# axiom_beta_plugin_module_1xHDMI_v0_2_543.net
KiCad netlist of a schematic drawn in EAGLE
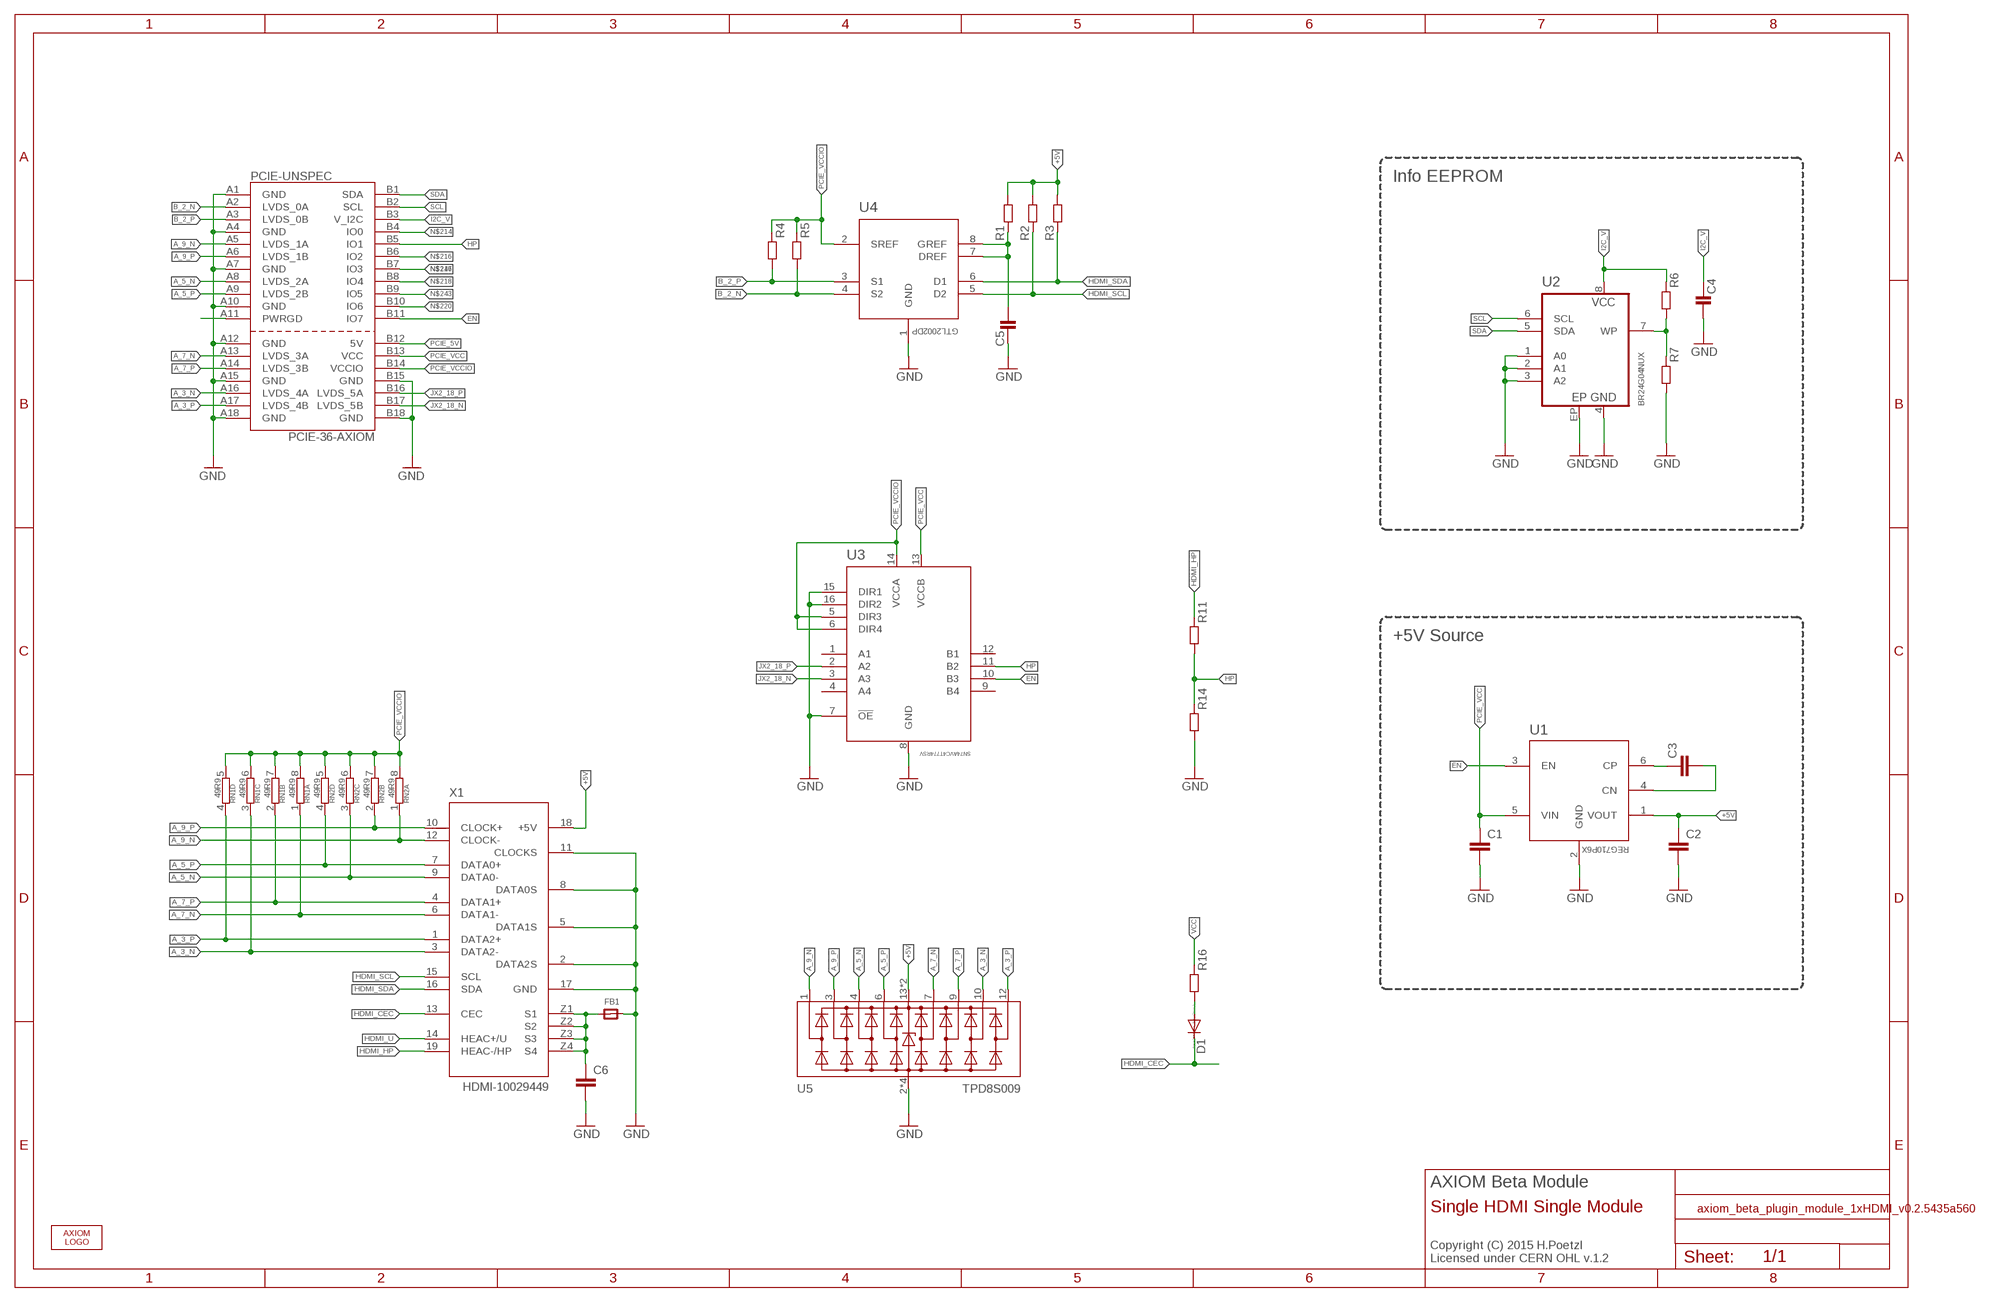
[diagram p0: schematic, sheet 1]

(export (version "E")
  (design (tool "Eeschema 10.0.6"))
  (components
    (comp (ref "C1")
      (value "C-EUC0603K")
      (footprint "eagle-import:C0603K")
      (libsource (lib "eagle-import") (part "C-EUC0603K"))
    )
    (comp (ref "C2")
      (value "C-EUC0603K")
      (footprint "eagle-import:C0603K")
      (libsource (lib "eagle-import") (part "C-EUC0603K"))
    )
    (comp (ref "C3")
      (value "C-EUC0603K")
      (footprint "eagle-import:C0603K")
      (libsource (lib "eagle-import") (part "C-EUC0603K"))
    )
    (comp (ref "C4")
      (value "C0402-B")
      (footprint "eagle-import:0402-B")
      (libsource (lib "eagle-import") (part "C0402-B"))
    )
    (comp (ref "C5")
      (value "C0402-B")
      (footprint "eagle-import:0402-B")
      (libsource (lib "eagle-import") (part "C0402-B"))
    )
    (comp (ref "C6")
      (value "C-EUC0603K")
      (footprint "eagle-import:C0603K")
      (libsource (lib "eagle-import") (part "C-EUC0603K"))
    )
    (comp (ref "D1")
      (value "DIODE-SOD523")
      (footprint "eagle-import:SOD523")
      (libsource (lib "eagle-import") (part "DIODE-SOD523"))
    )
    (comp (ref "FB1")
      (value "FERRITE_0603MP")
      (footprint "eagle-import:_0603MP")
      (libsource (lib "eagle-import") (part "FERRITE_0603MP"))
    )
    (comp (ref "PCIE-UNSPEC")
      (value "PCIE-36-AXIOM")
      (footprint "eagle-import:PCIE-36-AXIOM")
      (libsource (lib "eagle-import") (part "PCIE-36-AXIOM"))
    )
    (comp (ref "R1")
      (value "R0402-B")
      (footprint "eagle-import:0402-B")
      (libsource (lib "eagle-import") (part "R0402-B"))
    )
    (comp (ref "R2")
      (value "R0402-B")
      (footprint "eagle-import:0402-B")
      (libsource (lib "eagle-import") (part "R0402-B"))
    )
    (comp (ref "R3")
      (value "R0402-B")
      (footprint "eagle-import:0402-B")
      (libsource (lib "eagle-import") (part "R0402-B"))
    )
    (comp (ref "R4")
      (value "R0402-B")
      (footprint "eagle-import:0402-B")
      (libsource (lib "eagle-import") (part "R0402-B"))
    )
    (comp (ref "R5")
      (value "R0402-B")
      (footprint "eagle-import:0402-B")
      (libsource (lib "eagle-import") (part "R0402-B"))
    )
    (comp (ref "R6")
      (value "R0402-B")
      (footprint "eagle-import:0402-B")
      (libsource (lib "eagle-import") (part "R0402-B"))
    )
    (comp (ref "R7")
      (value "R0603-B")
      (footprint "eagle-import:0603-B")
      (libsource (lib "eagle-import") (part "R0603-B"))
    )
    (comp (ref "R11")
      (value "R0402-B")
      (footprint "eagle-import:0402-B")
      (libsource (lib "eagle-import") (part "R0402-B"))
    )
    (comp (ref "R14")
      (value "R0402-B")
      (footprint "eagle-import:0402-B")
      (libsource (lib "eagle-import") (part "R0402-B"))
    )
    (comp (ref "R16")
      (value "R0402-B")
      (footprint "eagle-import:0402-B")
      (libsource (lib "eagle-import") (part "R0402-B"))
    )
    (comp (ref "RN1")
      (value "49R9")
      (footprint "eagle-import:CAY16")
      (libsource (lib "eagle-import") (part "4R-NCAY16"))
    )
    (comp (ref "RN2")
      (value "49R9")
      (footprint "eagle-import:CAY16")
      (libsource (lib "eagle-import") (part "4R-NCAY16"))
    )
    (comp (ref "U$1")
      (value "AXIOM_LOGO262X40")
      (footprint "eagle-import:AXIOM_LOGO_262X40")
      (libsource (lib "eagle-import") (part "AXIOM_LOGO262X40"))
    )
    (comp (ref "U1")
      (value "REG710P6X")
      (footprint "eagle-import:SOT65P210X110-6N")
      (libsource (lib "eagle-import") (part "REG710P6X"))
    )
    (comp (ref "U2")
      (value "BR24G04NUX")
      (footprint "eagle-import:DFN200X300X100-9N")
      (libsource (lib "eagle-import") (part "BR24G04NUX"))
    )
    (comp (ref "U3")
      (value "SN74AVC4T774RSV")
      (footprint "eagle-import:QFN40P185X265X55-16N")
      (libsource (lib "eagle-import") (part "SN74AVC4T774RSV"))
    )
    (comp (ref "U4")
      (value "GTL2002DP")
      (footprint "eagle-import:TSSOP-8")
      (libsource (lib "eagle-import") (part "GTL2002DP"))
    )
    (comp (ref "U5")
      (value "TPD8S009")
      (footprint "eagle-import:R-PDSO-N15")
      (libsource (lib "eagle-import") (part "TPD8S009"))
    )
    (comp (ref "X1")
      (value "HDMI-10029449")
      (footprint "eagle-import:10029449-X01XLF")
      (libsource (lib "eagle-import") (part "HDMI-10029449"))
    )
  )
  (nets
    (net (code "1") (name "+5V") (class "Default")
      (node (ref "C2") (pin "1") (pinfunction "1_1") (pintype "passive"))
      (node (ref "R1") (pin "2") (pinfunction "2_2") (pintype "passive"))
      (node (ref "R2") (pin "2") (pinfunction "2_2") (pintype "passive"))
      (node (ref "R3") (pin "2") (pinfunction "2_2") (pintype "passive"))
      (node (ref "U1") (pin "1") (pinfunction "VOUT_1") (pintype "output"))
      (node (ref "U5") (pin "13") (pinfunction "VCC_13") (pintype "power_in"))
      (node (ref "U5") (pin "15") (pinfunction "VCC_15") (pintype "power_in"))
      (node (ref "X1") (pin "18") (pinfunction "+5V_18") (pintype "power_in"))
    )
    (net (code "2") (name "A_3_N") (class "Default")
      (node (ref "PCIE-UNSPEC") (pin "A16") (pinfunction "LVDS_4A_A16") (pintype "passive"))
      (node (ref "RN1") (pin "3") (pinfunction "1_3") (pintype "passive"))
      (node (ref "U5") (pin "10") (pinfunction "ESD7_10") (pintype "passive"))
      (node (ref "X1") (pin "3") (pinfunction "DATA2-_3") (pintype "bidirectional"))
    )
    (net (code "3") (name "A_3_P") (class "Default")
      (node (ref "PCIE-UNSPEC") (pin "A17") (pinfunction "LVDS_4B_A17") (pintype "passive"))
      (node (ref "RN1") (pin "4") (pinfunction "1_4") (pintype "passive"))
      (node (ref "U5") (pin "12") (pinfunction "ESD8_12") (pintype "passive"))
      (node (ref "X1") (pin "1") (pinfunction "DATA2+_1") (pintype "bidirectional"))
    )
    (net (code "4") (name "A_5_N") (class "Default")
      (node (ref "PCIE-UNSPEC") (pin "A8") (pinfunction "LVDS_2A_A8") (pintype "passive"))
      (node (ref "RN2") (pin "3") (pinfunction "1_3") (pintype "passive"))
      (node (ref "U5") (pin "4") (pinfunction "ESD3_4") (pintype "passive"))
      (node (ref "X1") (pin "9") (pinfunction "DATA0-_9") (pintype "bidirectional"))
    )
    (net (code "5") (name "A_5_P") (class "Default")
      (node (ref "PCIE-UNSPEC") (pin "A9") (pinfunction "LVDS_2B_A9") (pintype "passive"))
      (node (ref "RN2") (pin "4") (pinfunction "1_4") (pintype "passive"))
      (node (ref "U5") (pin "6") (pinfunction "ESD4_6") (pintype "passive"))
      (node (ref "X1") (pin "7") (pinfunction "DATA0+_7") (pintype "bidirectional"))
    )
    (net (code "6") (name "A_7_N") (class "Default")
      (node (ref "PCIE-UNSPEC") (pin "A13") (pinfunction "LVDS_3A_A13") (pintype "passive"))
      (node (ref "RN1") (pin "1") (pinfunction "1_1") (pintype "passive"))
      (node (ref "U5") (pin "7") (pinfunction "ESD5_7") (pintype "passive"))
      (node (ref "X1") (pin "6") (pinfunction "DATA1-_6") (pintype "bidirectional"))
    )
    (net (code "7") (name "A_7_P") (class "Default")
      (node (ref "PCIE-UNSPEC") (pin "A14") (pinfunction "LVDS_3B_A14") (pintype "passive"))
      (node (ref "RN1") (pin "2") (pinfunction "1_2") (pintype "passive"))
      (node (ref "U5") (pin "9") (pinfunction "ESD6_9") (pintype "passive"))
      (node (ref "X1") (pin "4") (pinfunction "DATA1+_4") (pintype "bidirectional"))
    )
    (net (code "8") (name "A_9_N") (class "Default")
      (node (ref "PCIE-UNSPEC") (pin "A5") (pinfunction "LVDS_1A_A5") (pintype "passive"))
      (node (ref "RN2") (pin "1") (pinfunction "1_1") (pintype "passive"))
      (node (ref "U5") (pin "1") (pinfunction "ESD1_1") (pintype "passive"))
      (node (ref "X1") (pin "12") (pinfunction "CLOCK-_12") (pintype "bidirectional"))
    )
    (net (code "9") (name "A_9_P") (class "Default")
      (node (ref "PCIE-UNSPEC") (pin "A6") (pinfunction "LVDS_1B_A6") (pintype "passive"))
      (node (ref "RN2") (pin "2") (pinfunction "1_2") (pintype "passive"))
      (node (ref "U5") (pin "3") (pinfunction "ESD2_3") (pintype "passive"))
      (node (ref "X1") (pin "10") (pinfunction "CLOCK+_10") (pintype "bidirectional"))
    )
    (net (code "10") (name "B_2_N") (class "Default")
      (node (ref "PCIE-UNSPEC") (pin "A2") (pinfunction "LVDS_0A_A2") (pintype "passive"))
      (node (ref "R5") (pin "2") (pinfunction "2_2") (pintype "passive"))
      (node (ref "U4") (pin "4") (pinfunction "S2_4") (pintype "bidirectional"))
    )
    (net (code "11") (name "B_2_P") (class "Default")
      (node (ref "PCIE-UNSPEC") (pin "A3") (pinfunction "LVDS_0B_A3") (pintype "passive"))
      (node (ref "R4") (pin "2") (pinfunction "2_2") (pintype "passive"))
      (node (ref "U4") (pin "3") (pinfunction "S1_3") (pintype "bidirectional"))
    )
    (net (code "12") (name "EN") (class "Default")
      (node (ref "PCIE-UNSPEC") (pin "B11") (pinfunction "IO7_B11") (pintype "passive"))
      (node (ref "U1") (pin "3") (pinfunction "EN_3") (pintype "input"))
      (node (ref "U3") (pin "10") (pinfunction "B3_10") (pintype "bidirectional"))
    )
    (net (code "13") (name "GND") (class "Default")
      (node (ref "C1") (pin "2") (pinfunction "2_2") (pintype "passive"))
      (node (ref "C2") (pin "2") (pinfunction "2_2") (pintype "passive"))
      (node (ref "C4") (pin "2") (pinfunction "2_2") (pintype "passive"))
      (node (ref "C5") (pin "1") (pinfunction "1_1") (pintype "passive"))
      (node (ref "C6") (pin "2") (pinfunction "2_2") (pintype "passive"))
      (node (ref "FB1") (pin "2") (pinfunction "P$2_2") (pintype "passive"))
      (node (ref "PCIE-UNSPEC") (pin "A1") (pinfunction "GND_A1") (pintype "passive"))
      (node (ref "PCIE-UNSPEC") (pin "A10") (pinfunction "GND_A10") (pintype "passive"))
      (node (ref "PCIE-UNSPEC") (pin "A12") (pinfunction "GND_A12") (pintype "passive"))
      (node (ref "PCIE-UNSPEC") (pin "A15") (pinfunction "GND_A15") (pintype "passive"))
      (node (ref "PCIE-UNSPEC") (pin "A18") (pinfunction "GND_A18") (pintype "passive"))
      (node (ref "PCIE-UNSPEC") (pin "A4") (pinfunction "GND_A4") (pintype "passive"))
      (node (ref "PCIE-UNSPEC") (pin "A7") (pinfunction "GND_A7") (pintype "passive"))
      (node (ref "PCIE-UNSPEC") (pin "B15") (pinfunction "GND_B15") (pintype "passive"))
      (node (ref "PCIE-UNSPEC") (pin "B18") (pinfunction "GND_B18") (pintype "passive"))
      (node (ref "R14") (pin "2") (pinfunction "2_2") (pintype "passive"))
      (node (ref "R7") (pin "2") (pinfunction "2_2") (pintype "passive"))
      (node (ref "U1") (pin "2") (pinfunction "GND_2") (pintype "passive"))
      (node (ref "U2") (pin "1") (pinfunction "A0_1") (pintype "input"))
      (node (ref "U2") (pin "2") (pinfunction "A1_2") (pintype "input"))
      (node (ref "U2") (pin "3") (pinfunction "A2_3") (pintype "input"))
      (node (ref "U2") (pin "4") (pinfunction "GND_4") (pintype "passive"))
      (node (ref "U2") (pin "EP") (pinfunction "EP_EP") (pintype "passive"))
      (node (ref "U3") (pin "15") (pinfunction "DIR1_15") (pintype "input"))
      (node (ref "U3") (pin "16") (pinfunction "DIR2_16") (pintype "input"))
      (node (ref "U3") (pin "7") (pinfunction "~{OE}_7") (pintype "input"))
      (node (ref "U3") (pin "8") (pinfunction "GND_8") (pintype "passive"))
      (node (ref "U4") (pin "1") (pinfunction "GND_1") (pintype "passive"))
      (node (ref "U5") (pin "11") (pinfunction "GND_11") (pintype "power_in"))
      (node (ref "U5") (pin "2") (pinfunction "GND_2") (pintype "power_in"))
      (node (ref "U5") (pin "5") (pinfunction "GND_5") (pintype "power_in"))
      (node (ref "U5") (pin "8") (pinfunction "GND_8") (pintype "power_in"))
      (node (ref "X1") (pin "11") (pinfunction "CLOCKS_11") (pintype "power_in"))
      (node (ref "X1") (pin "17") (pinfunction "GND_17") (pintype "bidirectional"))
      (node (ref "X1") (pin "2") (pinfunction "DATA2S_2") (pintype "power_in"))
      (node (ref "X1") (pin "5") (pinfunction "DATA1S_5") (pintype "power_in"))
      (node (ref "X1") (pin "8") (pinfunction "DATA0S_8") (pintype "power_in"))
    )
    (net (code "14") (name "HDMI_CEC") (class "Default")
      (node (ref "D1") (pin "C") (pinfunction "C_C") (pintype "passive"))
      (node (ref "X1") (pin "13") (pinfunction "CEC_13") (pintype "bidirectional"))
    )
    (net (code "15") (name "HDMI_HP") (class "Default")
      (node (ref "R11") (pin "1") (pinfunction "1_1") (pintype "passive"))
      (node (ref "X1") (pin "19") (pinfunction "HEAC-/HP_19") (pintype "bidirectional"))
    )
    (net (code "16") (name "HDMI_SCL") (class "Default")
      (node (ref "R2") (pin "1") (pinfunction "1_1") (pintype "passive"))
      (node (ref "U4") (pin "5") (pinfunction "D2_5") (pintype "bidirectional"))
      (node (ref "X1") (pin "15") (pinfunction "SCL_15") (pintype "bidirectional"))
    )
    (net (code "17") (name "HDMI_SDA") (class "Default")
      (node (ref "R3") (pin "1") (pinfunction "1_1") (pintype "passive"))
      (node (ref "U4") (pin "6") (pinfunction "D1_6") (pintype "bidirectional"))
      (node (ref "X1") (pin "16") (pinfunction "SDA_16") (pintype "bidirectional"))
    )
    (net (code "18") (name "HDMI_U") (class "Default")
      (node (ref "X1") (pin "14") (pinfunction "HEAC+/U_14") (pintype "bidirectional"))
    )
    (net (code "19") (name "HP") (class "Default")
      (node (ref "PCIE-UNSPEC") (pin "B5") (pinfunction "IO1_B5") (pintype "passive"))
      (node (ref "R11") (pin "2") (pinfunction "2_2") (pintype "passive"))
      (node (ref "R14") (pin "1") (pinfunction "1_1") (pintype "passive"))
      (node (ref "U3") (pin "11") (pinfunction "B2_11") (pintype "bidirectional"))
    )
    (net (code "20") (name "I2C_V") (class "Default")
      (node (ref "C4") (pin "1") (pinfunction "1_1") (pintype "passive"))
      (node (ref "PCIE-UNSPEC") (pin "B3") (pinfunction "V_I2C_B3") (pintype "passive"))
      (node (ref "R6") (pin "1") (pinfunction "1_1") (pintype "passive"))
      (node (ref "U2") (pin "8") (pinfunction "VCC_8") (pintype "power_in"))
    )
    (net (code "21") (name "JX2_18_N") (class "Default")
      (node (ref "PCIE-UNSPEC") (pin "B17") (pinfunction "LVDS_5B_B17") (pintype "passive"))
      (node (ref "U3") (pin "3") (pinfunction "A3_3") (pintype "bidirectional"))
    )
    (net (code "22") (name "JX2_18_P") (class "Default")
      (node (ref "PCIE-UNSPEC") (pin "B16") (pinfunction "LVDS_5A_B16") (pintype "passive"))
      (node (ref "U3") (pin "2") (pinfunction "A2_2") (pintype "bidirectional"))
    )
    (net (code "23") (name "N$214") (class "Default")
      (node (ref "PCIE-UNSPEC") (pin "B4") (pinfunction "IO0_B4") (pintype "passive"))
    )
    (net (code "24") (name "N$216") (class "Default")
      (node (ref "PCIE-UNSPEC") (pin "B6") (pinfunction "IO2_B6") (pintype "passive"))
    )
    (net (code "25") (name "N$218") (class "Default")
      (node (ref "PCIE-UNSPEC") (pin "B8") (pinfunction "IO4_B8") (pintype "passive"))
    )
    (net (code "26") (name "N$220") (class "Default")
      (node (ref "PCIE-UNSPEC") (pin "B10") (pinfunction "IO6_B10") (pintype "passive"))
    )
    (net (code "27") (name "N$243") (class "Default")
      (node (ref "PCIE-UNSPEC") (pin "B9") (pinfunction "IO5_B9") (pintype "passive"))
    )
    (net (code "28") (name "N$247") (class "Default")
      (node (ref "PCIE-UNSPEC") (pin "B7") (pinfunction "IO3_B7") (pintype "passive"))
    )
    (net (code "29") (name "Net-(D1-PadA)") (class "Default")
      (node (ref "D1") (pin "A") (pinfunction "A_A") (pintype "passive"))
      (node (ref "R16") (pin "2") (pinfunction "2_2") (pintype "passive"))
    )
    (net (code "30") (name "Net-(FB1-P$1)") (class "Default")
      (node (ref "C6") (pin "1") (pinfunction "1_1") (pintype "passive"))
      (node (ref "FB1") (pin "1") (pinfunction "P$1_1") (pintype "passive"))
      (node (ref "X1") (pin "Z1") (pinfunction "S1_Z1") (pintype "power_in"))
      (node (ref "X1") (pin "Z2") (pinfunction "S2_Z2") (pintype "power_in"))
      (node (ref "X1") (pin "Z3") (pinfunction "S3_Z3") (pintype "power_in"))
      (node (ref "X1") (pin "Z4") (pinfunction "S4_Z4") (pintype "power_in"))
    )
    (net (code "31") (name "Net-(U1-CN)") (class "Default")
      (node (ref "C3") (pin "2") (pinfunction "2_2") (pintype "passive"))
      (node (ref "U1") (pin "4") (pinfunction "CN_4") (pintype "power_in"))
    )
    (net (code "32") (name "Net-(U1-CP)") (class "Default")
      (node (ref "C3") (pin "1") (pinfunction "1_1") (pintype "passive"))
      (node (ref "U1") (pin "6") (pinfunction "CP_6") (pintype "output"))
    )
    (net (code "33") (name "Net-(U2-WP)") (class "Default")
      (node (ref "R6") (pin "2") (pinfunction "2_2") (pintype "passive"))
      (node (ref "R7") (pin "1") (pinfunction "1_1") (pintype "passive"))
      (node (ref "U2") (pin "7") (pinfunction "WP_7") (pintype "input"))
    )
    (net (code "34") (name "Net-(U4-DREF)") (class "Default")
      (node (ref "C5") (pin "2") (pinfunction "2_2") (pintype "passive"))
      (node (ref "R1") (pin "1") (pinfunction "1_1") (pintype "passive"))
      (node (ref "U4") (pin "7") (pinfunction "DREF_7") (pintype "passive"))
      (node (ref "U4") (pin "8") (pinfunction "GREF_8") (pintype "passive"))
    )
    (net (code "35") (name "PCIE_5V") (class "Default")
      (node (ref "PCIE-UNSPEC") (pin "B12") (pinfunction "5V_B12") (pintype "passive"))
    )
    (net (code "36") (name "PCIE_VCC") (class "Default")
      (node (ref "C1") (pin "1") (pinfunction "1_1") (pintype "passive"))
      (node (ref "PCIE-UNSPEC") (pin "B13") (pinfunction "VCC_B13") (pintype "passive"))
      (node (ref "U1") (pin "5") (pinfunction "VIN_5") (pintype "power_in"))
      (node (ref "U3") (pin "13") (pinfunction "VCCB_13") (pintype "power_in"))
    )
    (net (code "37") (name "PCIE_VCCIO") (class "Default")
      (node (ref "PCIE-UNSPEC") (pin "B14") (pinfunction "VCCIO_B14") (pintype "passive"))
      (node (ref "R4") (pin "1") (pinfunction "1_1") (pintype "passive"))
      (node (ref "R5") (pin "1") (pinfunction "1_1") (pintype "passive"))
      (node (ref "RN1") (pin "5") (pinfunction "2_5") (pintype "passive"))
      (node (ref "RN1") (pin "6") (pinfunction "2_6") (pintype "passive"))
      (node (ref "RN1") (pin "7") (pinfunction "2_7") (pintype "passive"))
      (node (ref "RN1") (pin "8") (pinfunction "2_8") (pintype "passive"))
      (node (ref "RN2") (pin "5") (pinfunction "2_5") (pintype "passive"))
      (node (ref "RN2") (pin "6") (pinfunction "2_6") (pintype "passive"))
      (node (ref "RN2") (pin "7") (pinfunction "2_7") (pintype "passive"))
      (node (ref "RN2") (pin "8") (pinfunction "2_8") (pintype "passive"))
      (node (ref "U3") (pin "14") (pinfunction "VCCA_14") (pintype "power_in"))
      (node (ref "U3") (pin "5") (pinfunction "DIR3_5") (pintype "input"))
      (node (ref "U3") (pin "6") (pinfunction "DIR4_6") (pintype "input"))
      (node (ref "U4") (pin "2") (pinfunction "SREF_2") (pintype "passive"))
    )
    (net (code "38") (name "SCL") (class "Default")
      (node (ref "PCIE-UNSPEC") (pin "B2") (pinfunction "SCL_B2") (pintype "passive"))
      (node (ref "U2") (pin "6") (pinfunction "SCL_6") (pintype "input"))
    )
    (net (code "39") (name "SDA") (class "Default")
      (node (ref "PCIE-UNSPEC") (pin "B1") (pinfunction "SDA_B1") (pintype "passive"))
      (node (ref "U2") (pin "5") (pinfunction "SDA_5") (pintype "bidirectional"))
    )
    (net (code "40") (name "VCC") (class "Default")
      (node (ref "R16") (pin "1") (pinfunction "1_1") (pintype "passive"))
    )
    (net (code "41") (name "unconnected-(PCIE-UNSPEC-PWRGD-PadA11)") (class "Default")
      (node (ref "PCIE-UNSPEC") (pin "A11") (pinfunction "PWRGD_A11") (pintype "passive"))
    )
    (net (code "42") (name "unconnected-(U3-A1-Pad1)") (class "Default")
      (node (ref "U3") (pin "1") (pinfunction "A1_1") (pintype "bidirectional"))
    )
    (net (code "43") (name "unconnected-(U3-A4-Pad4)") (class "Default")
      (node (ref "U3") (pin "4") (pinfunction "A4_4") (pintype "bidirectional"))
    )
    (net (code "44") (name "unconnected-(U3-B1-Pad12)") (class "Default")
      (node (ref "U3") (pin "12") (pinfunction "B1_12") (pintype "bidirectional"))
    )
    (net (code "45") (name "unconnected-(U3-B4-Pad9)") (class "Default")
      (node (ref "U3") (pin "9") (pinfunction "B4_9") (pintype "bidirectional"))
    )
  )
)
